# StepperModule.net
KiCad netlist of a schematic drawn in EAGLE
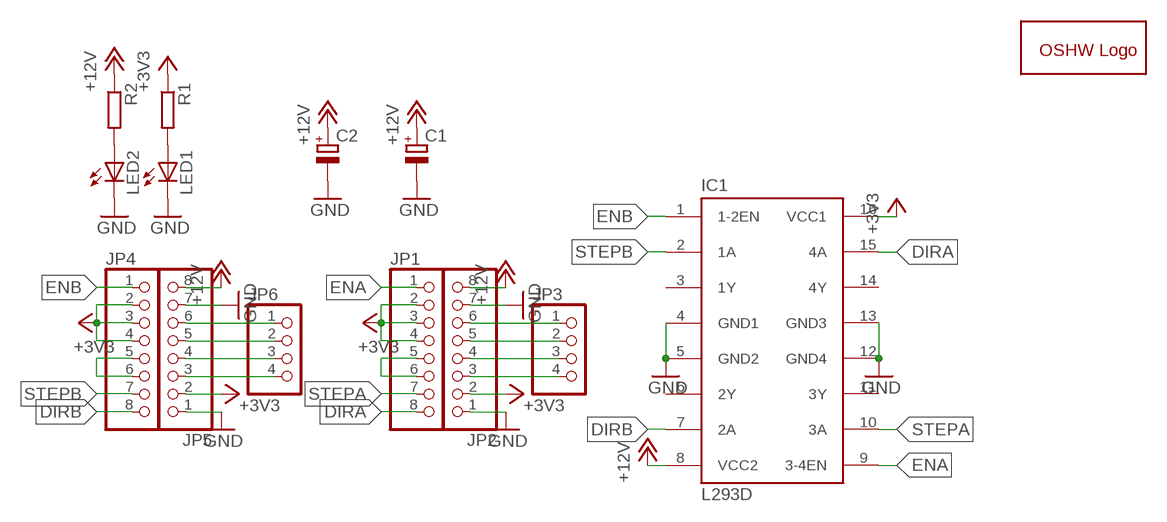
[diagram p0: schematic, sheet 1]

(export (version "E")
  (design (tool "Eeschema 10.0.6"))
  (components
    (comp (ref "C1")
      (value "CPOL-EUTT5D9")
      (footprint "eagle-import:TT5D9")
      (libsource (lib "eagle-import") (part "CPOL-EUTT5D9"))
    )
    (comp (ref "C2")
      (value "CPOL-EUTT5D9")
      (footprint "eagle-import:TT5D9")
      (libsource (lib "eagle-import") (part "CPOL-EUTT5D9"))
    )
    (comp (ref "IC1")
      (value "L293D")
      (footprint "eagle-import:L293")
      (libsource (lib "eagle-import") (part "L293D"))
    )
    (comp (ref "JP1")
      (value "PINHD-1X8")
      (footprint "eagle-import:1X08")
      (libsource (lib "eagle-import") (part "PINHD-1X8"))
    )
    (comp (ref "JP2")
      (value "PINHD-1X8")
      (footprint "eagle-import:1X08")
      (libsource (lib "eagle-import") (part "PINHD-1X8"))
    )
    (comp (ref "JP3")
      (value "PINHD-1X4")
      (footprint "eagle-import:1X04")
      (libsource (lib "eagle-import") (part "PINHD-1X4"))
    )
    (comp (ref "JP4")
      (value "PINHD-1X8")
      (footprint "eagle-import:1X08")
      (libsource (lib "eagle-import") (part "PINHD-1X8"))
    )
    (comp (ref "JP5")
      (value "PINHD-1X8")
      (footprint "eagle-import:1X08")
      (libsource (lib "eagle-import") (part "PINHD-1X8"))
    )
    (comp (ref "JP6")
      (value "PINHD-1X4")
      (footprint "eagle-import:1X04")
      (libsource (lib "eagle-import") (part "PINHD-1X4"))
    )
    (comp (ref "LED1")
      (value "LEDSML1206")
      (footprint "eagle-import:SML1206")
      (libsource (lib "eagle-import") (part "LEDSML1206"))
    )
    (comp (ref "LED2")
      (value "LEDSML1206")
      (footprint "eagle-import:SML1206")
      (libsource (lib "eagle-import") (part "LEDSML1206"))
    )
    (comp (ref "R1")
      (value "R-EU_M1206")
      (footprint "eagle-import:M1206")
      (libsource (lib "eagle-import") (part "R-EU_M1206"))
    )
    (comp (ref "R2")
      (value "R-EU_M1206")
      (footprint "eagle-import:M1206")
      (libsource (lib "eagle-import") (part "R-EU_M1206"))
    )
    (comp (ref "U$5")
      (value "OPENSOURCE")
      (footprint "eagle-import:OSHW_5MM")
      (libsource (lib "eagle-import") (part "OPENSOURCE"))
    )
  )
  (nets
    (net (code "1") (name "+3V3") (class "Default")
      (node (ref "IC1") (pin "16") (pinfunction "VCC1_16") (pintype "power_in"))
      (node (ref "JP1") (pin "2") (pinfunction "2_2") (pintype "passive"))
      (node (ref "JP1") (pin "3") (pinfunction "3_3") (pintype "passive"))
      (node (ref "JP1") (pin "4") (pinfunction "4_4") (pintype "passive"))
      (node (ref "JP2") (pin "2") (pinfunction "2_2") (pintype "passive"))
      (node (ref "JP4") (pin "2") (pinfunction "2_2") (pintype "passive"))
      (node (ref "JP4") (pin "3") (pinfunction "3_3") (pintype "passive"))
      (node (ref "JP4") (pin "4") (pinfunction "4_4") (pintype "passive"))
      (node (ref "JP5") (pin "2") (pinfunction "2_2") (pintype "passive"))
      (node (ref "R1") (pin "1") (pinfunction "1_1") (pintype "passive"))
    )
    (net (code "2") (name "+12V") (class "Default")
      (node (ref "C1") (pin "+") (pinfunction "+_+") (pintype "passive"))
      (node (ref "C2") (pin "+") (pinfunction "+_+") (pintype "passive"))
      (node (ref "IC1") (pin "8") (pinfunction "VCC2_8") (pintype "power_in"))
      (node (ref "JP2") (pin "8") (pinfunction "8_8") (pintype "passive"))
      (node (ref "JP5") (pin "8") (pinfunction "8_8") (pintype "passive"))
      (node (ref "R2") (pin "1") (pinfunction "1_1") (pintype "passive"))
    )
    (net (code "3") (name "DIRA") (class "Default")
      (node (ref "IC1") (pin "15") (pinfunction "4A_15") (pintype "input"))
      (node (ref "JP1") (pin "8") (pinfunction "8_8") (pintype "passive"))
    )
    (net (code "4") (name "DIRB") (class "Default")
      (node (ref "IC1") (pin "7") (pinfunction "2A_7") (pintype "input"))
      (node (ref "JP4") (pin "8") (pinfunction "8_8") (pintype "passive"))
    )
    (net (code "5") (name "ENA") (class "Default")
      (node (ref "IC1") (pin "9") (pinfunction "3-4EN_9") (pintype "input"))
      (node (ref "JP1") (pin "1") (pinfunction "1_1") (pintype "passive"))
    )
    (net (code "6") (name "ENB") (class "Default")
      (node (ref "IC1") (pin "1") (pinfunction "1-2EN_1") (pintype "input"))
      (node (ref "JP4") (pin "1") (pinfunction "1_1") (pintype "passive"))
    )
    (net (code "7") (name "GND") (class "Default")
      (node (ref "C1") (pin "-") (pinfunction "-_-") (pintype "passive"))
      (node (ref "C2") (pin "-") (pinfunction "-_-") (pintype "passive"))
      (node (ref "IC1") (pin "12") (pinfunction "GND4_12") (pintype "power_in"))
      (node (ref "IC1") (pin "13") (pinfunction "GND3_13") (pintype "power_in"))
      (node (ref "IC1") (pin "4") (pinfunction "GND1_4") (pintype "power_in"))
      (node (ref "IC1") (pin "5") (pinfunction "GND2_5") (pintype "power_in"))
      (node (ref "JP2") (pin "1") (pinfunction "1_1") (pintype "passive"))
      (node (ref "JP2") (pin "7") (pinfunction "7_7") (pintype "passive"))
      (node (ref "JP5") (pin "1") (pinfunction "1_1") (pintype "passive"))
      (node (ref "JP5") (pin "7") (pinfunction "7_7") (pintype "passive"))
      (node (ref "LED1") (pin "C") (pinfunction "C_C") (pintype "passive"))
      (node (ref "LED2") (pin "C") (pinfunction "C_C") (pintype "passive"))
    )
    (net (code "8") (name "Net-(JP1-Pad5)") (class "Default")
      (node (ref "JP1") (pin "5") (pinfunction "5_5") (pintype "passive"))
      (node (ref "JP1") (pin "6") (pinfunction "6_6") (pintype "passive"))
    )
    (net (code "9") (name "Net-(JP2-Pad3)") (class "Default")
      (node (ref "JP2") (pin "3") (pinfunction "3_3") (pintype "passive"))
      (node (ref "JP3") (pin "4") (pinfunction "4_4") (pintype "passive"))
    )
    (net (code "10") (name "Net-(JP2-Pad4)") (class "Default")
      (node (ref "JP2") (pin "4") (pinfunction "4_4") (pintype "passive"))
      (node (ref "JP3") (pin "3") (pinfunction "3_3") (pintype "passive"))
    )
    (net (code "11") (name "Net-(JP2-Pad5)") (class "Default")
      (node (ref "JP2") (pin "5") (pinfunction "5_5") (pintype "passive"))
      (node (ref "JP3") (pin "2") (pinfunction "2_2") (pintype "passive"))
    )
    (net (code "12") (name "Net-(JP2-Pad6)") (class "Default")
      (node (ref "JP2") (pin "6") (pinfunction "6_6") (pintype "passive"))
      (node (ref "JP3") (pin "1") (pinfunction "1_1") (pintype "passive"))
    )
    (net (code "13") (name "Net-(JP4-Pad5)") (class "Default")
      (node (ref "JP4") (pin "5") (pinfunction "5_5") (pintype "passive"))
      (node (ref "JP4") (pin "6") (pinfunction "6_6") (pintype "passive"))
    )
    (net (code "14") (name "Net-(JP5-Pad3)") (class "Default")
      (node (ref "JP5") (pin "3") (pinfunction "3_3") (pintype "passive"))
      (node (ref "JP6") (pin "4") (pinfunction "4_4") (pintype "passive"))
    )
    (net (code "15") (name "Net-(JP5-Pad4)") (class "Default")
      (node (ref "JP5") (pin "4") (pinfunction "4_4") (pintype "passive"))
      (node (ref "JP6") (pin "3") (pinfunction "3_3") (pintype "passive"))
    )
    (net (code "16") (name "Net-(JP5-Pad5)") (class "Default")
      (node (ref "JP5") (pin "5") (pinfunction "5_5") (pintype "passive"))
      (node (ref "JP6") (pin "2") (pinfunction "2_2") (pintype "passive"))
    )
    (net (code "17") (name "Net-(JP5-Pad6)") (class "Default")
      (node (ref "JP5") (pin "6") (pinfunction "6_6") (pintype "passive"))
      (node (ref "JP6") (pin "1") (pinfunction "1_1") (pintype "passive"))
    )
    (net (code "18") (name "Net-(LED1-PadA)") (class "Default")
      (node (ref "LED1") (pin "A") (pinfunction "A_A") (pintype "passive"))
      (node (ref "R1") (pin "2") (pinfunction "2_2") (pintype "passive"))
    )
    (net (code "19") (name "Net-(LED2-PadA)") (class "Default")
      (node (ref "LED2") (pin "A") (pinfunction "A_A") (pintype "passive"))
      (node (ref "R2") (pin "2") (pinfunction "2_2") (pintype "passive"))
    )
    (net (code "20") (name "STEPA") (class "Default")
      (node (ref "IC1") (pin "10") (pinfunction "3A_10") (pintype "input"))
      (node (ref "JP1") (pin "7") (pinfunction "7_7") (pintype "passive"))
    )
    (net (code "21") (name "STEPB") (class "Default")
      (node (ref "IC1") (pin "2") (pinfunction "1A_2") (pintype "input"))
      (node (ref "JP4") (pin "7") (pinfunction "7_7") (pintype "passive"))
    )
    (net (code "22") (name "unconnected-(IC1-1Y-Pad3)") (class "Default")
      (node (ref "IC1") (pin "3") (pinfunction "1Y_3") (pintype "output"))
    )
    (net (code "23") (name "unconnected-(IC1-2Y-Pad6)") (class "Default")
      (node (ref "IC1") (pin "6") (pinfunction "2Y_6") (pintype "output"))
    )
    (net (code "24") (name "unconnected-(IC1-3Y-Pad11)") (class "Default")
      (node (ref "IC1") (pin "11") (pinfunction "3Y_11") (pintype "output"))
    )
    (net (code "25") (name "unconnected-(IC1-4Y-Pad14)") (class "Default")
      (node (ref "IC1") (pin "14") (pinfunction "4Y_14") (pintype "output"))
    )
  )
)
